# LittleBrushed.net
KiCad netlist of a schematic drawn in EAGLE
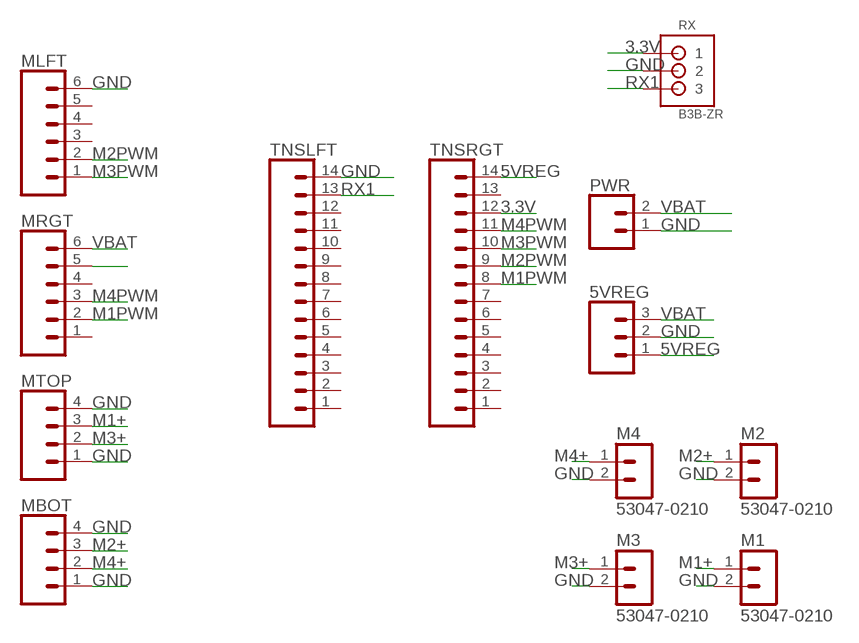
[diagram p0: schematic, sheet 1]

(export (version "E")
  (design (tool "Eeschema 10.0.6"))
  (components
    (comp (ref "5VREG")
      (value "CONN_03")
      (footprint "eagle-import:1X03")
      (libsource (lib "eagle-import") (part "CONN_03"))
    )
    (comp (ref "M1")
      (value "53047-0210")
      (footprint "eagle-import:53047-0210")
      (libsource (lib "eagle-import") (part "53047-0210"))
    )
    (comp (ref "M2")
      (value "53047-0210")
      (footprint "eagle-import:53047-0210")
      (libsource (lib "eagle-import") (part "53047-0210"))
    )
    (comp (ref "M3")
      (value "53047-0210")
      (footprint "eagle-import:53047-0210")
      (libsource (lib "eagle-import") (part "53047-0210"))
    )
    (comp (ref "M4")
      (value "53047-0210")
      (footprint "eagle-import:53047-0210")
      (libsource (lib "eagle-import") (part "53047-0210"))
    )
    (comp (ref "MBOT")
      (value "CONN_04")
      (footprint "eagle-import:1X04")
      (libsource (lib "eagle-import") (part "CONN_04"))
    )
    (comp (ref "MLFT")
      (value "CONN_06NO_SILK_FEMALE_PTH")
      (footprint "eagle-import:1X06_NO_SILK")
      (libsource (lib "eagle-import") (part "CONN_06NO_SILK_FEMALE_PTH"))
    )
    (comp (ref "MRGT")
      (value "CONN_06NO_SILK_FEMALE_PTH")
      (footprint "eagle-import:1X06_NO_SILK")
      (libsource (lib "eagle-import") (part "CONN_06NO_SILK_FEMALE_PTH"))
    )
    (comp (ref "MTOP")
      (value "CONN_04")
      (footprint "eagle-import:1X04")
      (libsource (lib "eagle-import") (part "CONN_04"))
    )
    (comp (ref "PWR")
      (value "CONN_02")
      (footprint "eagle-import:1X02")
      (libsource (lib "eagle-import") (part "CONN_02"))
    )
    (comp (ref "RX")
      (value "B3B-ZR")
      (footprint "eagle-import:B3B-ZR")
      (libsource (lib "eagle-import") (part "B3B-ZR"))
    )
    (comp (ref "TNSLFT")
      (value "CONN_14")
      (footprint "eagle-import:1X14")
      (libsource (lib "eagle-import") (part "CONN_14"))
    )
    (comp (ref "TNSRGT")
      (value "CONN_14")
      (footprint "eagle-import:1X14")
      (libsource (lib "eagle-import") (part "CONN_14"))
    )
  )
  (nets
    (net (code "1") (name "/3.3V") (class "Default")
      (node (ref "RX") (pin "1") (pinfunction "1_1") (pintype "bidirectional"))
      (node (ref "TNSRGT") (pin "12") (pinfunction "12_12") (pintype "passive"))
    )
    (net (code "2") (name "/5VREG") (class "Default")
      (node (ref "5VREG") (pin "1") (pinfunction "1_1") (pintype "passive"))
      (node (ref "TNSRGT") (pin "14") (pinfunction "14_14") (pintype "passive"))
    )
    (net (code "3") (name "/GND") (class "Default")
      (node (ref "5VREG") (pin "2") (pinfunction "2_2") (pintype "passive"))
      (node (ref "M1") (pin "2") (pinfunction "2_2") (pintype "passive"))
      (node (ref "M2") (pin "2") (pinfunction "2_2") (pintype "passive"))
      (node (ref "M3") (pin "2") (pinfunction "2_2") (pintype "passive"))
      (node (ref "M4") (pin "2") (pinfunction "2_2") (pintype "passive"))
      (node (ref "MBOT") (pin "1") (pinfunction "1_1") (pintype "passive"))
      (node (ref "MBOT") (pin "4") (pinfunction "4_4") (pintype "passive"))
      (node (ref "MLFT") (pin "6") (pinfunction "6_6") (pintype "passive"))
      (node (ref "MTOP") (pin "1") (pinfunction "1_1") (pintype "passive"))
      (node (ref "MTOP") (pin "4") (pinfunction "4_4") (pintype "passive"))
      (node (ref "PWR") (pin "1") (pinfunction "1_1") (pintype "passive"))
      (node (ref "RX") (pin "2") (pinfunction "2_2") (pintype "bidirectional"))
      (node (ref "TNSLFT") (pin "14") (pinfunction "14_14") (pintype "passive"))
    )
    (net (code "4") (name "/M1+") (class "Default")
      (node (ref "M1") (pin "1") (pinfunction "1_1") (pintype "passive"))
      (node (ref "MTOP") (pin "3") (pinfunction "3_3") (pintype "passive"))
    )
    (net (code "5") (name "/M1PWM") (class "Default")
      (node (ref "MRGT") (pin "2") (pinfunction "2_2") (pintype "passive"))
      (node (ref "TNSRGT") (pin "8") (pinfunction "8_8") (pintype "passive"))
    )
    (net (code "6") (name "/M2+") (class "Default")
      (node (ref "M2") (pin "1") (pinfunction "1_1") (pintype "passive"))
      (node (ref "MBOT") (pin "3") (pinfunction "3_3") (pintype "passive"))
    )
    (net (code "7") (name "/M2PWM") (class "Default")
      (node (ref "MLFT") (pin "2") (pinfunction "2_2") (pintype "passive"))
      (node (ref "TNSRGT") (pin "9") (pinfunction "9_9") (pintype "passive"))
    )
    (net (code "8") (name "/M3+") (class "Default")
      (node (ref "M3") (pin "1") (pinfunction "1_1") (pintype "passive"))
      (node (ref "MTOP") (pin "2") (pinfunction "2_2") (pintype "passive"))
    )
    (net (code "9") (name "/M3PWM") (class "Default")
      (node (ref "MLFT") (pin "1") (pinfunction "1_1") (pintype "passive"))
      (node (ref "TNSRGT") (pin "10") (pinfunction "10_10") (pintype "passive"))
    )
    (net (code "10") (name "/M4+") (class "Default")
      (node (ref "M4") (pin "1") (pinfunction "1_1") (pintype "passive"))
      (node (ref "MBOT") (pin "2") (pinfunction "2_2") (pintype "passive"))
    )
    (net (code "11") (name "/M4PWM") (class "Default")
      (node (ref "MRGT") (pin "3") (pinfunction "3_3") (pintype "passive"))
      (node (ref "TNSRGT") (pin "11") (pinfunction "11_11") (pintype "passive"))
    )
    (net (code "12") (name "/RX1") (class "Default")
      (node (ref "RX") (pin "3") (pinfunction "3_3") (pintype "bidirectional"))
      (node (ref "TNSLFT") (pin "13") (pinfunction "13_13") (pintype "passive"))
    )
    (net (code "13") (name "/VBAT") (class "Default")
      (node (ref "5VREG") (pin "3") (pinfunction "3_3") (pintype "passive"))
      (node (ref "MRGT") (pin "6") (pinfunction "6_6") (pintype "passive"))
      (node (ref "PWR") (pin "2") (pinfunction "2_2") (pintype "passive"))
    )
    (net (code "14") (name "unconnected-(MLFT-Pad3)") (class "Default")
      (node (ref "MLFT") (pin "3") (pinfunction "3_3") (pintype "passive"))
    )
    (net (code "15") (name "unconnected-(MLFT-Pad4)") (class "Default")
      (node (ref "MLFT") (pin "4") (pinfunction "4_4") (pintype "passive"))
    )
    (net (code "16") (name "unconnected-(MLFT-Pad5)") (class "Default")
      (node (ref "MLFT") (pin "5") (pinfunction "5_5") (pintype "passive"))
    )
    (net (code "17") (name "unconnected-(MRGT-Pad1)") (class "Default")
      (node (ref "MRGT") (pin "1") (pinfunction "1_1") (pintype "passive"))
    )
    (net (code "18") (name "unconnected-(MRGT-Pad4)") (class "Default")
      (node (ref "MRGT") (pin "4") (pinfunction "4_4") (pintype "passive"))
    )
    (net (code "19") (name "unconnected-(MRGT-Pad5)") (class "Default")
      (node (ref "MRGT") (pin "5") (pinfunction "5_5") (pintype "passive"))
    )
    (net (code "20") (name "unconnected-(TNSLFT-Pad1)") (class "Default")
      (node (ref "TNSLFT") (pin "1") (pinfunction "1_1") (pintype "passive"))
    )
    (net (code "21") (name "unconnected-(TNSLFT-Pad2)") (class "Default")
      (node (ref "TNSLFT") (pin "2") (pinfunction "2_2") (pintype "passive"))
    )
    (net (code "22") (name "unconnected-(TNSLFT-Pad3)") (class "Default")
      (node (ref "TNSLFT") (pin "3") (pinfunction "3_3") (pintype "passive"))
    )
    (net (code "23") (name "unconnected-(TNSLFT-Pad4)") (class "Default")
      (node (ref "TNSLFT") (pin "4") (pinfunction "4_4") (pintype "passive"))
    )
    (net (code "24") (name "unconnected-(TNSLFT-Pad5)") (class "Default")
      (node (ref "TNSLFT") (pin "5") (pinfunction "5_5") (pintype "passive"))
    )
    (net (code "25") (name "unconnected-(TNSLFT-Pad6)") (class "Default")
      (node (ref "TNSLFT") (pin "6") (pinfunction "6_6") (pintype "passive"))
    )
    (net (code "26") (name "unconnected-(TNSLFT-Pad7)") (class "Default")
      (node (ref "TNSLFT") (pin "7") (pinfunction "7_7") (pintype "passive"))
    )
    (net (code "27") (name "unconnected-(TNSLFT-Pad8)") (class "Default")
      (node (ref "TNSLFT") (pin "8") (pinfunction "8_8") (pintype "passive"))
    )
    (net (code "28") (name "unconnected-(TNSLFT-Pad9)") (class "Default")
      (node (ref "TNSLFT") (pin "9") (pinfunction "9_9") (pintype "passive"))
    )
    (net (code "29") (name "unconnected-(TNSLFT-Pad10)") (class "Default")
      (node (ref "TNSLFT") (pin "10") (pinfunction "10_10") (pintype "passive"))
    )
    (net (code "30") (name "unconnected-(TNSLFT-Pad11)") (class "Default")
      (node (ref "TNSLFT") (pin "11") (pinfunction "11_11") (pintype "passive"))
    )
    (net (code "31") (name "unconnected-(TNSLFT-Pad12)") (class "Default")
      (node (ref "TNSLFT") (pin "12") (pinfunction "12_12") (pintype "passive"))
    )
    (net (code "32") (name "unconnected-(TNSRGT-Pad1)") (class "Default")
      (node (ref "TNSRGT") (pin "1") (pinfunction "1_1") (pintype "passive"))
    )
    (net (code "33") (name "unconnected-(TNSRGT-Pad2)") (class "Default")
      (node (ref "TNSRGT") (pin "2") (pinfunction "2_2") (pintype "passive"))
    )
    (net (code "34") (name "unconnected-(TNSRGT-Pad3)") (class "Default")
      (node (ref "TNSRGT") (pin "3") (pinfunction "3_3") (pintype "passive"))
    )
    (net (code "35") (name "unconnected-(TNSRGT-Pad4)") (class "Default")
      (node (ref "TNSRGT") (pin "4") (pinfunction "4_4") (pintype "passive"))
    )
    (net (code "36") (name "unconnected-(TNSRGT-Pad5)") (class "Default")
      (node (ref "TNSRGT") (pin "5") (pinfunction "5_5") (pintype "passive"))
    )
    (net (code "37") (name "unconnected-(TNSRGT-Pad6)") (class "Default")
      (node (ref "TNSRGT") (pin "6") (pinfunction "6_6") (pintype "passive"))
    )
    (net (code "38") (name "unconnected-(TNSRGT-Pad7)") (class "Default")
      (node (ref "TNSRGT") (pin "7") (pinfunction "7_7") (pintype "passive"))
    )
    (net (code "39") (name "unconnected-(TNSRGT-Pad13)") (class "Default")
      (node (ref "TNSRGT") (pin "13") (pinfunction "13_13") (pintype "passive"))
    )
  )
)
